# cyberdriver_rev2.net
KiCad netlist of a schematic drawn in EAGLE
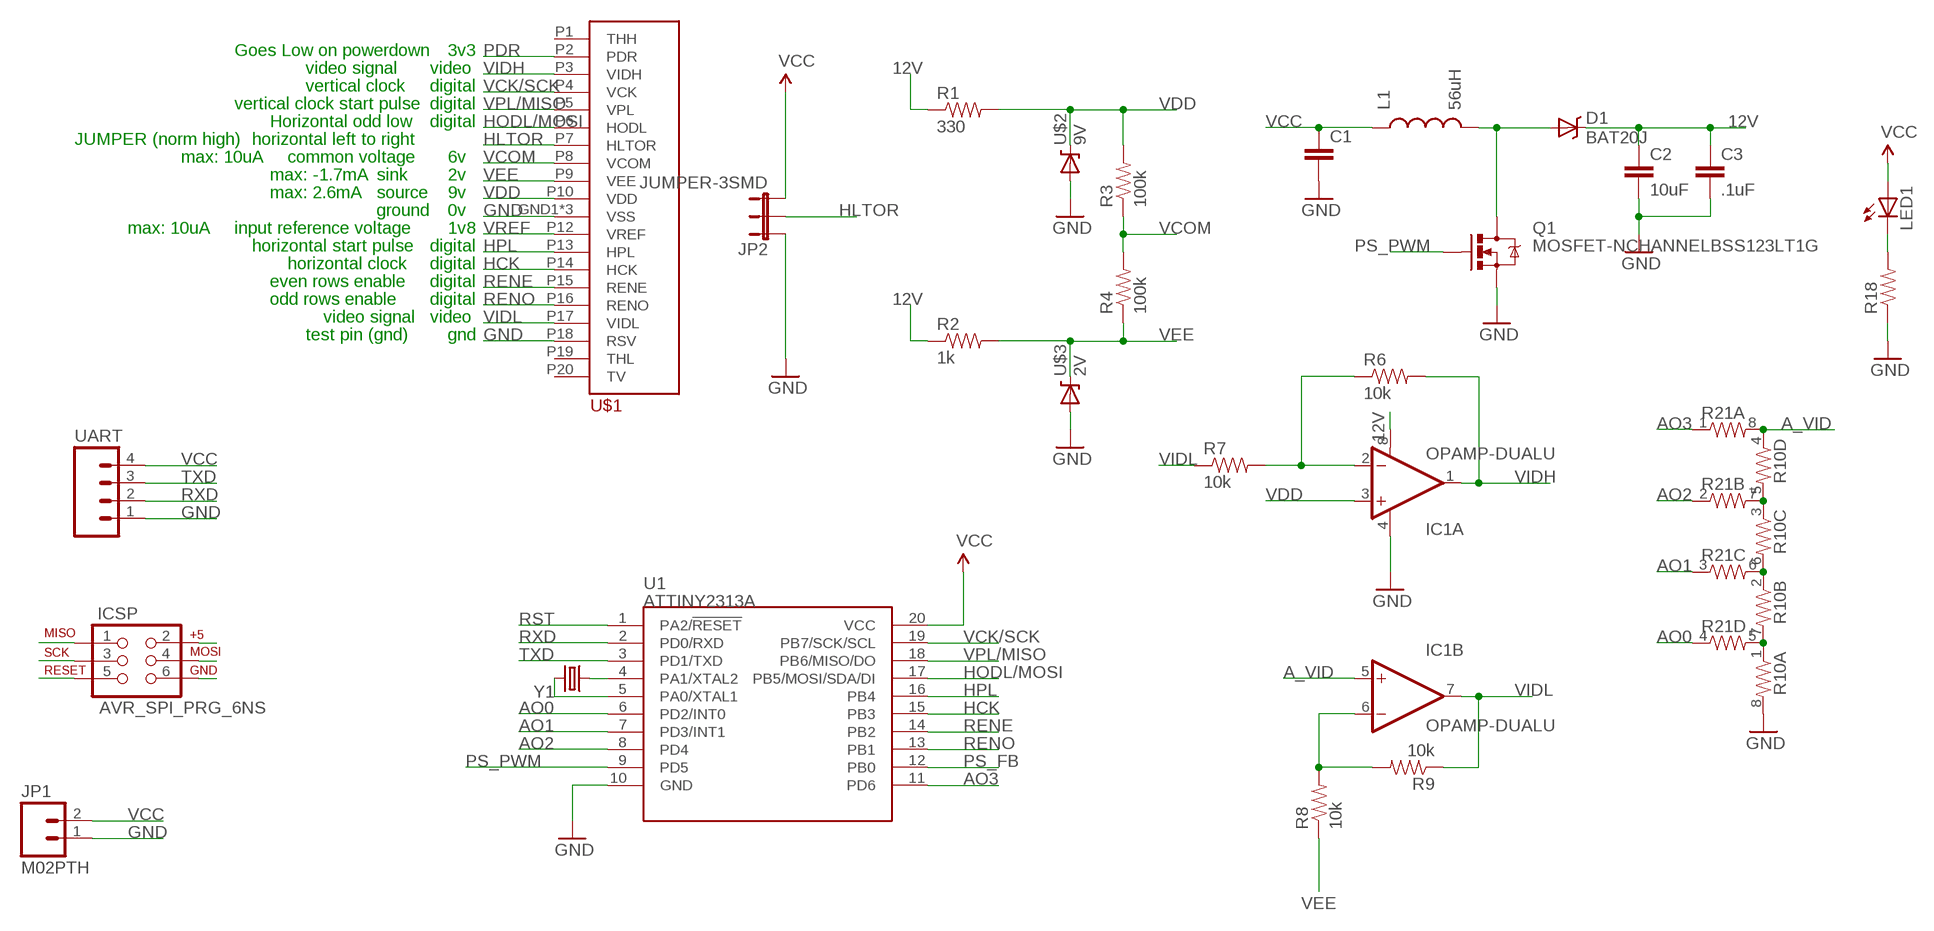
[diagram p0: schematic, sheet 1]

(export (version "E")
  (design (tool "Eeschema 10.0.6"))
  (components
    (comp (ref "C1")
      (value "CAP1206")
      (footprint "eagle-import:1206")
      (libsource (lib "eagle-import") (part "CAP1206"))
    )
    (comp (ref "C2")
      (value "10uF")
      (footprint "eagle-import:1210")
      (libsource (lib "eagle-import") (part "cyberdriver_CAP1210"))
    )
    (comp (ref "C3")
      (value ".1uF")
      (footprint "eagle-import:0603-CAP")
      (libsource (lib "eagle-import") (part "cyberdriver_CAP0603-CAP"))
    )
    (comp (ref "D1")
      (value "BAT20J")
      (footprint "eagle-import:SOD-323")
      (libsource (lib "eagle-import") (part "DIODE-SCHOTTKY-BAT20J"))
    )
    (comp (ref "IC1")
      (value "OPAMP-DUALU")
      (footprint "eagle-import:SO08")
      (libsource (lib "eagle-import") (part "OPAMP-DUALU"))
    )
    (comp (ref "ICSP")
      (value "AVR_SPI_PRG_6NS")
      (footprint "eagle-import:2X3-NS")
      (libsource (lib "eagle-import") (part "AVR_SPI_PRG_6NS"))
    )
    (comp (ref "JP1")
      (value "M02PTH")
      (footprint "eagle-import:1X02")
      (libsource (lib "eagle-import") (part "M02PTH"))
    )
    (comp (ref "JP2")
      (value "JUMPER-3SMD")
      (footprint "eagle-import:SJ_3")
      (libsource (lib "eagle-import") (part "JUMPER-3SMD"))
    )
    (comp (ref "L1")
      (value "56uH")
      (footprint "eagle-import:SDR0403")
      (libsource (lib "eagle-import") (part "INDUCTORSDR0403-560KL"))
    )
    (comp (ref "LED1")
      (value "LED1206")
      (footprint "eagle-import:LED-1206")
      (libsource (lib "eagle-import") (part "LED1206"))
    )
    (comp (ref "Q1")
      (value "MOSFET-NCHANNELBSS123LT1G")
      (footprint "eagle-import:SOT23")
      (libsource (lib "eagle-import") (part "MOSFET-NCHANNELBSS123LT1G"))
    )
    (comp (ref "R1")
      (value "330")
      (footprint "eagle-import:0603-RES")
      (libsource (lib "eagle-import") (part "RESISTOR0603-RES"))
    )
    (comp (ref "R2")
      (value "1k")
      (footprint "eagle-import:0603-RES")
      (libsource (lib "eagle-import") (part "RESISTOR0603-RES"))
    )
    (comp (ref "R3")
      (value "100k")
      (footprint "eagle-import:0603-RES")
      (libsource (lib "eagle-import") (part "RESISTOR0603-RES"))
    )
    (comp (ref "R4")
      (value "100k")
      (footprint "eagle-import:0603-RES")
      (libsource (lib "eagle-import") (part "RESISTOR0603-RES"))
    )
    (comp (ref "R6")
      (value "10k")
      (footprint "eagle-import:0603-RES")
      (libsource (lib "eagle-import") (part "RESISTOR0603-RES"))
    )
    (comp (ref "R7")
      (value "10k")
      (footprint "eagle-import:0603-RES")
      (libsource (lib "eagle-import") (part "RESISTOR0603-RES"))
    )
    (comp (ref "R8")
      (value "10k")
      (footprint "eagle-import:0603-RES")
      (libsource (lib "eagle-import") (part "RESISTOR0603-RES"))
    )
    (comp (ref "R9")
      (value "10k")
      (footprint "eagle-import:0603-RES")
      (libsource (lib "eagle-import") (part "RESISTOR0603-RES"))
    )
    (comp (ref "R10")
      (value "RESISTOR-ARRAY0603-ARV")
      (footprint "eagle-import:0603-ARV")
      (libsource (lib "eagle-import") (part "RESISTOR-ARRAY0603-ARV"))
    )
    (comp (ref "R18")
      (value "RESISTOR0805-RES")
      (footprint "eagle-import:0805")
      (libsource (lib "eagle-import") (part "RESISTOR0805-RES"))
    )
    (comp (ref "R21")
      (value "RESISTOR-ARRAY0603-ARV")
      (footprint "eagle-import:0603-ARV")
      (libsource (lib "eagle-import") (part "RESISTOR-ARRAY0603-ARV"))
    )
    (comp (ref "U$1")
      (value "CYBERDISPLAY-CONN")
      (footprint "eagle-import:MOLEX-54550-2071")
      (libsource (lib "eagle-import") (part "CYBERDISPLAY-CONN"))
    )
    (comp (ref "U$2")
      (value "9V")
      (footprint "eagle-import:SOD-323")
      (libsource (lib "eagle-import") (part "DIODE-ZENER-BZT52"))
    )
    (comp (ref "U$3")
      (value "2V")
      (footprint "eagle-import:SOD-323")
      (libsource (lib "eagle-import") (part "DIODE-ZENER-BZT52"))
    )
    (comp (ref "U1")
      (value "ATTINY2313A")
      (footprint "eagle-import:SOP20W")
      (libsource (lib "eagle-import") (part "ATTINY2313A"))
    )
    (comp (ref "UART")
      (value "M041.27MM")
      (footprint "eagle-import:1X04-1.27MM")
      (libsource (lib "eagle-import") (part "M041.27MM"))
    )
    (comp (ref "Y1")
      (value "CRYSTAL5X3")
      (footprint "eagle-import:CRYSTAL-SMD-5X3")
      (libsource (lib "eagle-import") (part "CRYSTAL5X3"))
    )
  )
  (nets
    (net (code "1") (name "/12V") (class "Default")
      (node (ref "C2") (pin "1") (pinfunction "1_1") (pintype "passive"))
      (node (ref "C3") (pin "1") (pinfunction "1_1") (pintype "passive"))
      (node (ref "D1") (pin "C") (pinfunction "C_C") (pintype "passive"))
      (node (ref "IC1") (pin "8") (pinfunction "V+_8") (pintype "power_in"))
      (node (ref "R1") (pin "1") (pinfunction "1_1") (pintype "passive"))
      (node (ref "R2") (pin "1") (pinfunction "1_1") (pintype "passive"))
    )
    (net (code "2") (name "/AO0") (class "Default")
      (node (ref "R21") (pin "4") (pinfunction "1_4") (pintype "passive"))
      (node (ref "U1") (pin "6") (pinfunction "PD2/INT0_6") (pintype "bidirectional"))
    )
    (net (code "3") (name "/AO1") (class "Default")
      (node (ref "R21") (pin "3") (pinfunction "1_3") (pintype "passive"))
      (node (ref "U1") (pin "7") (pinfunction "PD3/INT1_7") (pintype "bidirectional"))
    )
    (net (code "4") (name "/AO2") (class "Default")
      (node (ref "R21") (pin "2") (pinfunction "1_2") (pintype "passive"))
      (node (ref "U1") (pin "8") (pinfunction "PD4_8") (pintype "bidirectional"))
    )
    (net (code "5") (name "/AO3") (class "Default")
      (node (ref "R21") (pin "1") (pinfunction "1_1") (pintype "passive"))
      (node (ref "U1") (pin "11") (pinfunction "PD6_11") (pintype "bidirectional"))
    )
    (net (code "6") (name "/A_VID") (class "Default")
      (node (ref "IC1") (pin "5") (pinfunction "+IN_5") (pintype "input"))
      (node (ref "R10") (pin "4") (pinfunction "1_4") (pintype "passive"))
      (node (ref "R21") (pin "8") (pinfunction "2_8") (pintype "passive"))
    )
    (net (code "7") (name "/HCK") (class "Default")
      (node (ref "U$1") (pin "P14") (pinfunction "HCK_P14") (pintype "bidirectional"))
      (node (ref "U1") (pin "15") (pinfunction "PB3_15") (pintype "bidirectional"))
    )
    (net (code "8") (name "/HLTOR") (class "Default")
      (node (ref "JP2") (pin "2") (pinfunction "2_2") (pintype "passive"))
      (node (ref "U$1") (pin "P7") (pinfunction "HLTOR_P7") (pintype "bidirectional"))
    )
    (net (code "9") (name "/HODL{slash}MOSI") (class "Default")
      (node (ref "ICSP") (pin "4") (pinfunction "4_4") (pintype "passive"))
      (node (ref "U$1") (pin "P6") (pinfunction "HODL_P6") (pintype "bidirectional"))
      (node (ref "U1") (pin "17") (pinfunction "PB5/MOSI/SDA/DI_17") (pintype "bidirectional"))
    )
    (net (code "10") (name "/HPL") (class "Default")
      (node (ref "U$1") (pin "P13") (pinfunction "HPL_P13") (pintype "bidirectional"))
      (node (ref "U1") (pin "16") (pinfunction "PB4_16") (pintype "bidirectional"))
    )
    (net (code "11") (name "/PDR") (class "Default")
      (node (ref "U$1") (pin "P2") (pinfunction "PDR_P2") (pintype "bidirectional"))
    )
    (net (code "12") (name "/PS_FB") (class "Default")
      (node (ref "U1") (pin "12") (pinfunction "PB0_12") (pintype "bidirectional"))
    )
    (net (code "13") (name "/PS_PWM") (class "Default")
      (node (ref "Q1") (pin "1") (pinfunction "G_1") (pintype "passive"))
      (node (ref "U1") (pin "9") (pinfunction "PD5_9") (pintype "bidirectional"))
    )
    (net (code "14") (name "/RENE") (class "Default")
      (node (ref "U$1") (pin "P15") (pinfunction "RENE_P15") (pintype "bidirectional"))
      (node (ref "U1") (pin "14") (pinfunction "PB2_14") (pintype "bidirectional"))
    )
    (net (code "15") (name "/RENO") (class "Default")
      (node (ref "U$1") (pin "P16") (pinfunction "RENO_P16") (pintype "bidirectional"))
      (node (ref "U1") (pin "13") (pinfunction "PB1_13") (pintype "bidirectional"))
    )
    (net (code "16") (name "/RST") (class "Default")
      (node (ref "ICSP") (pin "5") (pinfunction "5_5") (pintype "passive"))
      (node (ref "U1") (pin "1") (pinfunction "PA2/~{RESET}_1") (pintype "bidirectional"))
    )
    (net (code "17") (name "/RXD") (class "Default")
      (node (ref "U1") (pin "2") (pinfunction "PD0/RXD_2") (pintype "bidirectional"))
      (node (ref "UART") (pin "2") (pinfunction "2_2") (pintype "passive"))
    )
    (net (code "18") (name "/TXD") (class "Default")
      (node (ref "U1") (pin "3") (pinfunction "PD1/TXD_3") (pintype "bidirectional"))
      (node (ref "UART") (pin "3") (pinfunction "3_3") (pintype "passive"))
    )
    (net (code "19") (name "/VCK{slash}SCK") (class "Default")
      (node (ref "ICSP") (pin "3") (pinfunction "3_3") (pintype "passive"))
      (node (ref "U$1") (pin "P4") (pinfunction "VCK_P4") (pintype "bidirectional"))
      (node (ref "U1") (pin "19") (pinfunction "PB7/SCK/SCL_19") (pintype "bidirectional"))
    )
    (net (code "20") (name "/VCOM") (class "Default")
      (node (ref "R3") (pin "1") (pinfunction "1_1") (pintype "passive"))
      (node (ref "R4") (pin "2") (pinfunction "2_2") (pintype "passive"))
      (node (ref "U$1") (pin "P8") (pinfunction "VCOM_P8") (pintype "bidirectional"))
    )
    (net (code "21") (name "/VDD") (class "Default")
      (node (ref "IC1") (pin "3") (pinfunction "+IN_3") (pintype "input"))
      (node (ref "R1") (pin "2") (pinfunction "2_2") (pintype "passive"))
      (node (ref "R3") (pin "2") (pinfunction "2_2") (pintype "passive"))
      (node (ref "U$1") (pin "P10") (pinfunction "VDD_P10") (pintype "bidirectional"))
      (node (ref "U$2") (pin "C") (pinfunction "C_C") (pintype "passive"))
    )
    (net (code "22") (name "/VEE") (class "Default")
      (node (ref "R2") (pin "2") (pinfunction "2_2") (pintype "passive"))
      (node (ref "R4") (pin "1") (pinfunction "1_1") (pintype "passive"))
      (node (ref "R8") (pin "1") (pinfunction "1_1") (pintype "passive"))
      (node (ref "U$1") (pin "P9") (pinfunction "VEE_P9") (pintype "bidirectional"))
      (node (ref "U$3") (pin "C") (pinfunction "C_C") (pintype "passive"))
    )
    (net (code "23") (name "/VIDH") (class "Default")
      (node (ref "IC1") (pin "1") (pinfunction "OUT_1") (pintype "output"))
      (node (ref "R6") (pin "2") (pinfunction "2_2") (pintype "passive"))
      (node (ref "U$1") (pin "P3") (pinfunction "VIDH_P3") (pintype "bidirectional"))
    )
    (net (code "24") (name "/VIDL") (class "Default")
      (node (ref "IC1") (pin "7") (pinfunction "OUT_7") (pintype "output"))
      (node (ref "R7") (pin "1") (pinfunction "1_1") (pintype "passive"))
      (node (ref "R9") (pin "1") (pinfunction "1_1") (pintype "passive"))
      (node (ref "U$1") (pin "P17") (pinfunction "VIDL_P17") (pintype "bidirectional"))
    )
    (net (code "25") (name "/VPL{slash}MISO") (class "Default")
      (node (ref "ICSP") (pin "1") (pinfunction "1_1") (pintype "passive"))
      (node (ref "U$1") (pin "P5") (pinfunction "VPL_P5") (pintype "bidirectional"))
      (node (ref "U1") (pin "18") (pinfunction "PB6/MISO/DO_18") (pintype "bidirectional"))
    )
    (net (code "26") (name "/VREF") (class "Default")
      (node (ref "U$1") (pin "P12") (pinfunction "VREF_P12") (pintype "bidirectional"))
    )
    (net (code "27") (name "GND") (class "Default")
      (node (ref "C1") (pin "2") (pinfunction "2_2") (pintype "passive"))
      (node (ref "C2") (pin "2") (pinfunction "2_2") (pintype "passive"))
      (node (ref "C3") (pin "2") (pinfunction "2_2") (pintype "passive"))
      (node (ref "IC1") (pin "4") (pinfunction "V-_4") (pintype "power_in"))
      (node (ref "ICSP") (pin "6") (pinfunction "6_6") (pintype "passive"))
      (node (ref "JP1") (pin "1") (pinfunction "1_1") (pintype "passive"))
      (node (ref "JP2") (pin "1") (pinfunction "1_1") (pintype "passive"))
      (node (ref "Q1") (pin "2") (pinfunction "S_2") (pintype "passive"))
      (node (ref "R10") (pin "8") (pinfunction "2_8") (pintype "passive"))
      (node (ref "R18") (pin "1") (pinfunction "1_1") (pintype "passive"))
      (node (ref "U$1") (pin "GND1") (pinfunction "VSS_GND1") (pintype "bidirectional"))
      (node (ref "U$1") (pin "GND20") (pinfunction "VSS_GND20") (pintype "bidirectional"))
      (node (ref "U$1") (pin "P11") (pinfunction "VSS_P11") (pintype "bidirectional"))
      (node (ref "U$1") (pin "P18") (pinfunction "RSV_P18") (pintype "bidirectional"))
      (node (ref "U$2") (pin "A") (pinfunction "A_A") (pintype "passive"))
      (node (ref "U$3") (pin "A") (pinfunction "A_A") (pintype "passive"))
      (node (ref "U1") (pin "10") (pinfunction "GND_10") (pintype "bidirectional"))
      (node (ref "UART") (pin "1") (pinfunction "1_1") (pintype "passive"))
    )
    (net (code "28") (name "Net-(IC1A--IN)") (class "Default")
      (node (ref "IC1") (pin "2") (pinfunction "-IN_2") (pintype "input"))
      (node (ref "R6") (pin "1") (pinfunction "1_1") (pintype "passive"))
      (node (ref "R7") (pin "2") (pinfunction "2_2") (pintype "passive"))
    )
    (net (code "29") (name "Net-(IC1B--IN)") (class "Default")
      (node (ref "IC1") (pin "6") (pinfunction "-IN_6") (pintype "input"))
      (node (ref "R8") (pin "2") (pinfunction "2_2") (pintype "passive"))
      (node (ref "R9") (pin "2") (pinfunction "2_2") (pintype "passive"))
    )
    (net (code "30") (name "Net-(L1-2)") (class "Default")
      (node (ref "D1") (pin "A") (pinfunction "A_A") (pintype "passive"))
      (node (ref "L1") (pin "P$2") (pinfunction "2_P$2") (pintype "passive"))
      (node (ref "Q1") (pin "3") (pinfunction "D_3") (pintype "passive"))
    )
    (net (code "31") (name "Net-(LED1-PadC)") (class "Default")
      (node (ref "LED1") (pin "C") (pinfunction "C_C") (pintype "passive"))
      (node (ref "R18") (pin "2") (pinfunction "2_2") (pintype "passive"))
    )
    (net (code "32") (name "Net-(R10B-1)") (class "Default")
      (node (ref "R10") (pin "2") (pinfunction "1_2") (pintype "passive"))
      (node (ref "R10") (pin "6") (pinfunction "2_6") (pintype "passive"))
      (node (ref "R21") (pin "6") (pinfunction "2_6") (pintype "passive"))
    )
    (net (code "33") (name "Net-(R10B-2)") (class "Default")
      (node (ref "R10") (pin "1") (pinfunction "1_1") (pintype "passive"))
      (node (ref "R10") (pin "7") (pinfunction "2_7") (pintype "passive"))
      (node (ref "R21") (pin "5") (pinfunction "2_5") (pintype "passive"))
    )
    (net (code "34") (name "Net-(R10C-1)") (class "Default")
      (node (ref "R10") (pin "3") (pinfunction "1_3") (pintype "passive"))
      (node (ref "R10") (pin "5") (pinfunction "2_5") (pintype "passive"))
      (node (ref "R21") (pin "7") (pinfunction "2_7") (pintype "passive"))
    )
    (net (code "35") (name "Net-(U1-PA0{slash}XTAL1)") (class "Default")
      (node (ref "U1") (pin "5") (pinfunction "PA0/XTAL1_5") (pintype "bidirectional"))
      (node (ref "Y1") (pin "3") (pinfunction "2_3") (pintype "passive"))
    )
    (net (code "36") (name "Net-(U1-PA1{slash}XTAL2)") (class "Default")
      (node (ref "U1") (pin "4") (pinfunction "PA1/XTAL2_4") (pintype "bidirectional"))
      (node (ref "Y1") (pin "1") (pinfunction "1_1") (pintype "passive"))
    )
    (net (code "37") (name "VCC") (class "Default")
      (node (ref "C1") (pin "1") (pinfunction "1_1") (pintype "passive"))
      (node (ref "ICSP") (pin "2") (pinfunction "2_2") (pintype "passive"))
      (node (ref "JP1") (pin "2") (pinfunction "2_2") (pintype "passive"))
      (node (ref "JP2") (pin "3") (pinfunction "3_3") (pintype "passive"))
      (node (ref "L1") (pin "P$1") (pinfunction "1_P$1") (pintype "passive"))
      (node (ref "LED1") (pin "A") (pinfunction "A_A") (pintype "passive"))
      (node (ref "U1") (pin "20") (pinfunction "VCC_20") (pintype "bidirectional"))
      (node (ref "UART") (pin "4") (pinfunction "4_4") (pintype "passive"))
    )
    (net (code "38") (name "unconnected-(U$1-THH-PadP1)") (class "Default")
      (node (ref "U$1") (pin "P1") (pinfunction "THH_P1") (pintype "bidirectional"))
    )
    (net (code "39") (name "unconnected-(U$1-THL-PadP19)") (class "Default")
      (node (ref "U$1") (pin "P19") (pinfunction "THL_P19") (pintype "bidirectional"))
    )
    (net (code "40") (name "unconnected-(U$1-TV-PadP20)") (class "Default")
      (node (ref "U$1") (pin "P20") (pinfunction "TV_P20") (pintype "bidirectional"))
    )
  )
)
